# Sch_DA1.net
KiCad netlist of a schematic drawn in Altium Designer
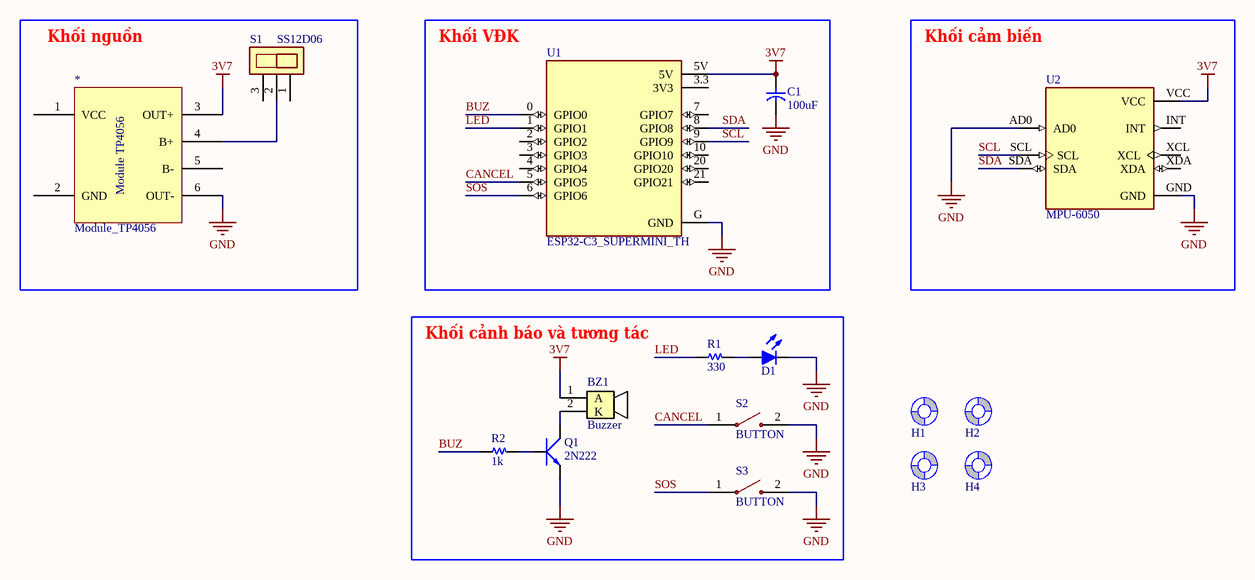
[diagram p0: Sch_DA1.SchDoc]

(export (version "E")
  (design (tool "Eeschema 10.0.6"))
  (components
    (comp (ref "*")
      (value "Module_TP4056")
      (footprint "Module_TP4056")
      (libsource (lib "Module_TP4056") (part "Module_TP4056"))
    )
    (comp (ref "BZ1") (value "Buzzer") (footprint "BUZZER") (libsource (lib "chipfc_libs") (part "Buzzer")))
    (comp (ref "C1")
      (value "100uF")
      (footprint "CYL/D.250/LS.100")
      (description "Capacitor pol")
      (libsource (lib "chipfc_libs") (part "Capacitor"))
    )
    (comp (ref "D1")
      (value "Led")
      (footprint "LED 5MM - RED")
      (description "Typical LED")
      (libsource (lib "led") (part "Led"))
    )
    (comp (ref "H1")
      (value "Screw Hole")
      (footprint "SCREW/3.0/6.0")
      (libsource (lib "chipfc_libs") (part "Screw Hole"))
    )
    (comp (ref "H2")
      (value "Screw Hole")
      (footprint "SCREW/3.0/6.0")
      (libsource (lib "chipfc_libs") (part "Screw Hole"))
    )
    (comp (ref "H3")
      (value "Screw Hole")
      (footprint "SCREW/3.0/6.0")
      (libsource (lib "chipfc_libs") (part "Screw Hole"))
    )
    (comp (ref "H4")
      (value "Screw Hole")
      (footprint "SCREW/3.0/6.0")
      (libsource (lib "chipfc_libs") (part "Screw Hole"))
    )
    (comp (ref "Q1")
      (value "2N222")
      (footprint "TO92-123")
      (description "NPN 600mW, ECB")
      (libsource (lib "Altium Library") (part "2N222"))
    )
    (comp (ref "R1")
      (value "330")
      (footprint "R 1/4W/300")
      (description "Resistor")
      (libsource (lib "chipfc_libs") (part "Resistor"))
    )
    (comp (ref "R2")
      (value "1k")
      (footprint "R 1/4W/300")
      (description "Resistor")
      (libsource (lib "chipfc_libs") (part "Resistor"))
    )
    (comp (ref "S1")
      (value "SS12D06")
      (footprint "SS12D06")
      (description "Lying Slide Switch 3 Pins.")
      (libsource (lib "Buttons & Switches") (part "SS12D06"))
    )
    (comp (ref "S2")
      (value "BUTTON")
      (footprint "PUSH_BUTTON_6X6")
      (description "Push Button Tactile Switch PTH 4 Pins 6x6mm.")
      (libsource (lib "Buttons & Switches") (part "PUSH_BUTTON_6X6"))
    )
    (comp (ref "S3")
      (value "BUTTON")
      (footprint "PUSH_BUTTON_6X6")
      (description "Push Button Tactile Switch PTH 4 Pins 6x6mm.")
      (libsource (lib "Buttons & Switches") (part "PUSH_BUTTON_6X6"))
    )
    (comp (ref "U1")
      (value "ESP32-C3_SUPERMINI_TH")
      (footprint "MODULE_ESP32-C3_SUPERMINI_TH")
      (description "Super tiny ESP32-C3 board")
      (fields (field (name "MF") "Espressif Systems") (field (name "MP") "ESP32-C3 SuperMini_TH"))
      (libsource (lib "ESP32-C3_SUPERMINI_TH") (part "ESP32-C3_SUPERMINI_TH"))
    )
    (comp (ref "U2")
      (value "MPU-6050")
      (footprint "MODULE_GY-521")
      (description "Triple Axis Accelerometer Gyro Breakout")
      (fields (field (name "MF") "GODREAM FORDREAM CO., LIMITED") (field (name "MP") "GY-521"))
      (libsource (lib "GY-521") (part "GY-521"))
    )
  )
  (nets
    (net (code "1") (name "/BUZ") (class "Default")
      (node (ref "R2") (pin "1") (pinfunction "1_1") (pintype "passive"))
      (node (ref "U1") (pin "0") (pinfunction "GPIO0_0") (pintype "bidirectional"))
    )
    (net (code "2") (name "/CANCEL") (class "Default")
      (node (ref "S2") (pin "1") (pinfunction "1_1") (pintype "passive"))
      (node (ref "U1") (pin "5") (pinfunction "GPIO5_5") (pintype "bidirectional"))
    )
    (net (code "3") (name "/LED") (class "Default")
      (node (ref "R1") (pin "1") (pinfunction "1_1") (pintype "passive"))
      (node (ref "U1") (pin "1") (pinfunction "GPIO1_1") (pintype "bidirectional"))
    )
    (net (code "4") (name "/SCL") (class "Default")
      (node (ref "U1") (pin "9") (pinfunction "GPIO9_9") (pintype "bidirectional"))
      (node (ref "U2") (pin "SCL") (pinfunction "SCL_SCL") (pintype "input"))
    )
    (net (code "5") (name "/SDA") (class "Default")
      (node (ref "U1") (pin "8") (pinfunction "GPIO8_8") (pintype "bidirectional"))
      (node (ref "U2") (pin "SDA") (pinfunction "SDA_SDA") (pintype "bidirectional"))
    )
    (net (code "6") (name "/SOS") (class "Default")
      (node (ref "S3") (pin "1") (pinfunction "1_1") (pintype "passive"))
      (node (ref "U1") (pin "6") (pinfunction "GPIO6_6") (pintype "bidirectional"))
    )
    (net (code "7") (name "3V7") (class "Default")
      (node (ref "*") (pin "3") (pinfunction "OUT+_3") (pintype "passive"))
      (node (ref "BZ1") (pin "1") (pinfunction "A_1") (pintype "passive"))
      (node (ref "C1") (pin "1") (pinfunction "1_1") (pintype "passive"))
      (node (ref "U1") (pin "5V") (pinfunction "5V_5V") (pintype "power_in"))
      (node (ref "U2") (pin "VCC") (pinfunction "VCC_VCC") (pintype "power_in"))
    )
    (net (code "8") (name "GND") (class "Default")
      (node (ref "*") (pin "6") (pinfunction "OUT-_6") (pintype "passive"))
      (node (ref "C1") (pin "2") (pinfunction "2_2") (pintype "passive"))
      (node (ref "D1") (pin "2") (pinfunction "K_2") (pintype "passive"))
      (node (ref "Q1") (pin "1") (pinfunction "E_1") (pintype "passive"))
      (node (ref "S2") (pin "2") (pinfunction "2_2") (pintype "passive"))
      (node (ref "S3") (pin "2") (pinfunction "2_2") (pintype "passive"))
      (node (ref "U1") (pin "G") (pinfunction "GND_G") (pintype "power_in"))
      (node (ref "U2") (pin "AD0") (pinfunction "AD0_AD0") (pintype "input"))
      (node (ref "U2") (pin "GND") (pinfunction "GND_GND") (pintype "power_in"))
    )
    (net (code "9") (name "Net-(*-B+)") (class "Default")
      (node (ref "*") (pin "4") (pinfunction "B+_4") (pintype "passive"))
      (node (ref "S1") (pin "2") (pintype "passive"))
    )
    (net (code "10") (name "Net-(BZ1-K)") (class "Default")
      (node (ref "BZ1") (pin "2") (pinfunction "K_2") (pintype "passive"))
      (node (ref "Q1") (pin "3") (pinfunction "C_3") (pintype "passive"))
    )
    (net (code "11") (name "Net-(D1-A)") (class "Default")
      (node (ref "D1") (pin "1") (pinfunction "A_1") (pintype "passive"))
      (node (ref "R1") (pin "2") (pinfunction "2_2") (pintype "passive"))
    )
    (net (code "12") (name "Net-(Q1-B)") (class "Default")
      (node (ref "Q1") (pin "2") (pinfunction "B_2") (pintype "passive"))
      (node (ref "R2") (pin "2") (pinfunction "2_2") (pintype "passive"))
    )
    (net (code "13") (name "unconnected-(*-B--Pad5)") (class "Default")
      (node (ref "*") (pin "5") (pinfunction "B-_5") (pintype "passive"))
    )
    (net (code "14") (name "unconnected-(*-GND-Pad2)") (class "Default")
      (node (ref "*") (pin "2") (pinfunction "GND_2") (pintype "passive"))
    )
    (net (code "15") (name "unconnected-(*-VCC-Pad1)") (class "Default")
      (node (ref "*") (pin "1") (pinfunction "VCC_1") (pintype "passive"))
    )
    (net (code "16") (name "unconnected-(H1-Screw-Pad1)") (class "Default")
      (node (ref "H1") (pin "1") (pinfunction "Screw_1") (pintype "passive"))
    )
    (net (code "17") (name "unconnected-(H2-Screw-Pad1)") (class "Default")
      (node (ref "H2") (pin "1") (pinfunction "Screw_1") (pintype "passive"))
    )
    (net (code "18") (name "unconnected-(H3-Screw-Pad1)") (class "Default")
      (node (ref "H3") (pin "1") (pinfunction "Screw_1") (pintype "passive"))
    )
    (net (code "19") (name "unconnected-(H4-Screw-Pad1)") (class "Default")
      (node (ref "H4") (pin "1") (pinfunction "Screw_1") (pintype "passive"))
    )
    (net (code "20") (name "unconnected-(S1-Pad1)") (class "Default")
      (node (ref "S1") (pin "1") (pintype "passive"))
    )
    (net (code "21") (name "unconnected-(S1-Pad3)") (class "Default")
      (node (ref "S1") (pin "3") (pintype "passive"))
    )
    (net (code "22") (name "unconnected-(U1-3V3-Pad3.3)") (class "Default")
      (node (ref "U1") (pin "3.3") (pinfunction "3V3_3.3") (pintype "power_in"))
    )
    (net (code "23") (name "unconnected-(U1-GPIO2-Pad2)") (class "Default")
      (node (ref "U1") (pin "2") (pinfunction "GPIO2_2") (pintype "bidirectional"))
    )
    (net (code "24") (name "unconnected-(U1-GPIO3-Pad3)") (class "Default")
      (node (ref "U1") (pin "3") (pinfunction "GPIO3_3") (pintype "bidirectional"))
    )
    (net (code "25") (name "unconnected-(U1-GPIO4-Pad4)") (class "Default")
      (node (ref "U1") (pin "4") (pinfunction "GPIO4_4") (pintype "bidirectional"))
    )
    (net (code "26") (name "unconnected-(U1-GPIO7-Pad7)") (class "Default")
      (node (ref "U1") (pin "7") (pinfunction "GPIO7_7") (pintype "bidirectional"))
    )
    (net (code "27") (name "unconnected-(U1-GPIO10-Pad10)") (class "Default")
      (node (ref "U1") (pin "10") (pinfunction "GPIO10_10") (pintype "bidirectional"))
    )
    (net (code "28") (name "unconnected-(U1-GPIO20-Pad20)") (class "Default")
      (node (ref "U1") (pin "20") (pinfunction "GPIO20_20") (pintype "bidirectional"))
    )
    (net (code "29") (name "unconnected-(U1-GPIO21-Pad21)") (class "Default")
      (node (ref "U1") (pin "21") (pinfunction "GPIO21_21") (pintype "bidirectional"))
    )
    (net (code "30") (name "unconnected-(U2-PadINT)") (class "Default")
      (node (ref "U2") (pin "INT") (pinfunction "INT_INT") (pintype "output"))
    )
    (net (code "31") (name "unconnected-(U2-PadXCL)") (class "Default")
      (node (ref "U2") (pin "XCL") (pinfunction "XCL_XCL") (pintype "output"))
    )
    (net (code "32") (name "unconnected-(U2-PadXDA)") (class "Default")
      (node (ref "U2") (pin "XDA") (pinfunction "XDA_XDA") (pintype "bidirectional"))
    )
  )
)
